# USB-C_BENCH_PSU.net
KiCad netlist of a schematic drawn in Altium Designer
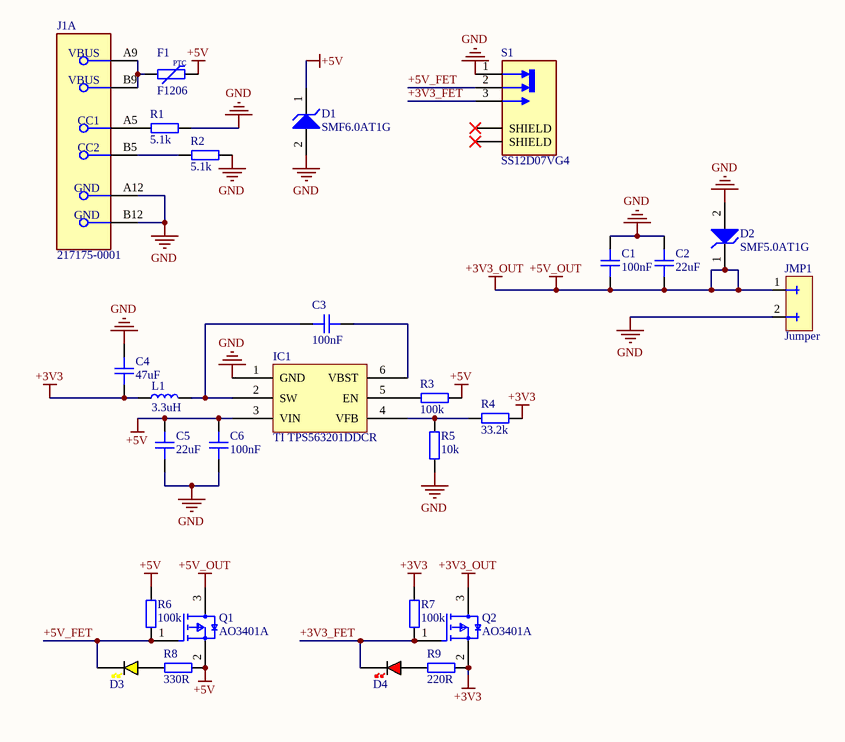
[diagram p0: USB-C_BENCH_PSU.SchDoc]

(export (version "E")
  (design (tool "Eeschema 10.0.6"))
  (components
    (comp (ref "C1")
      (value "100nF")
      (footprint "CAP_0402")
      (description "Capacitor SMD 0402")
      (libsource (lib "Schematic-Lib") (part "CAP_0402"))
    )
    (comp (ref "C2")
      (value "22uF")
      (footprint "CAP_0603")
      (description "Capacitor SMD 0603")
      (libsource (lib "Schematic-Lib") (part "CAP_0603"))
    )
    (comp (ref "C3")
      (value "100nF")
      (footprint "CAP_0402")
      (description "Capacitor SMD 0402")
      (libsource (lib "Schematic-Lib") (part "CAP_0402"))
    )
    (comp (ref "C4")
      (value "47uF")
      (footprint "CAP_0805")
      (description "Capacitor SMD 0805")
      (libsource (lib "Schematic-Lib") (part "CAP_0805"))
    )
    (comp (ref "C5")
      (value "22uF")
      (footprint "CAP_0603")
      (description "Capacitor SMD 0603")
      (libsource (lib "Schematic-Lib") (part "CAP_0603"))
    )
    (comp (ref "C6")
      (value "100nF")
      (footprint "CAP_0402")
      (description "Capacitor SMD 0402")
      (libsource (lib "Schematic-Lib") (part "CAP_0402"))
    )
    (comp (ref "D1")
      (value "SMF6.0AT1G")
      (footprint "ONSC-SOD-123FL-2-498_V")
      (description "200 W Transient Voltage Suppressor, 2-Pin SOD-123FL, Pb-Free, Tape and Reel")
      (fields (field (name "PARTNUMBER") "SMF5.0AT1G") (field (name "MANUFACTURER") "On Semiconductor"))
      (libsource (lib "Altium Content Vault") (part "ONSC-K1A2-2"))
    )
    (comp (ref "D2")
      (value "SMF5.0AT1G")
      (footprint "ONSC-SOD-123FL-2-498_V")
      (description "200 W Transient Voltage Suppressor, 2-Pin SOD-123FL, Pb-Free, Tape and Reel")
      (fields (field (name "MANUFACTURER") "On Semiconductor"))
      (libsource (lib "Altium Content Vault") (part "ONSC-K1A2-2"))
    )
    (comp (ref "D3")
      (value "WHITE")
      (footprint "LED_0603_YELLOW")
      (description "LED 0603 WHITE SMD")
      (libsource (lib "Schematic-Lib") (part "LED_0603_YELLOW"))
    )
    (comp (ref "D4")
      (value "RED")
      (footprint "LED_0603_RED")
      (description "LED 0603 RED SMD")
      (libsource (lib "Schematic-Lib") (part "LED_0603_RED"))
    )
    (comp (ref "F1")
      (value "F1206")
      (footprint "FUSE_1206")
      (description "Fuse PPTC SMD 1206")
      (libsource (lib "Schematic-Lib") (part "FUSE_PPTC_1206"))
    )
    (comp (ref "IC1")
      (value "TI TPS563201DDCR")
      (footprint "TI TPS563201DDCR")
      (libsource (lib "Custom_Components") (part "TI TPS563201DDCR"))
    )
    (comp (ref "J1")
      (value "217175-0001")
      (footprint "FP-217175-0001-MFG")
      (description "CONN RCP USB2.0 C 6+18P SMD RA")
      (libsource (lib "Altium Content Vault") (part "6a66c69350f09309f94811689c98437"))
    )
    (comp (ref "JMP1")
      (value "Jumper")
      (footprint "JMP2_TH")
      (description "Jumper 2 Pins Through-Hole DO NOT PLACE")
      (libsource (lib "Schematic-Lib") (part "JMP2_TH"))
    )
    (comp (ref "L1")
      (value "3.3uH")
      (footprint "IND_1008")
      (description "Inductor SMD 1008")
      (libsource (lib "Schematic-Lib") (part "IND_1008"))
    )
    (comp (ref "Q1")
      (value "AO3401A")
      (footprint "FP-SOT23-IPC_B")
      (description "MOSFET P-CH 30V SOT23")
      (libsource (lib "Altium Content Vault") (part "d876440acba04c58a9f817a20952145"))
    )
    (comp (ref "Q2")
      (value "AO3401A")
      (footprint "FP-SOT23-IPC_B")
      (description "MOSFET P-CH 30V SOT23")
      (libsource (lib "Altium Content Vault") (part "d876440acba04c58a9f817a20952145"))
    )
    (comp (ref "R1")
      (value "5.1k")
      (footprint "RES_0402")
      (description "Resistor SMD 0402")
      (libsource (lib "Schematic-Lib") (part "RES_0402"))
    )
    (comp (ref "R2")
      (value "5.1k")
      (footprint "RES_0402")
      (description "Resistor SMD 0402")
      (libsource (lib "Schematic-Lib") (part "RES_0402"))
    )
    (comp (ref "R3")
      (value "100k")
      (footprint "RES_0402")
      (description "Resistor SMD 0402")
      (libsource (lib "Schematic-Lib") (part "RES_0402"))
    )
    (comp (ref "R4")
      (value "33.2k")
      (footprint "RES_0402")
      (description "Resistor SMD 0402")
      (libsource (lib "Schematic-Lib") (part "RES_0402"))
    )
    (comp (ref "R5")
      (value "10k")
      (footprint "RES_0402")
      (description "Resistor SMD 0402")
      (libsource (lib "Schematic-Lib") (part "RES_0402"))
    )
    (comp (ref "R6")
      (value "100k")
      (footprint "RES_0402")
      (description "Resistor SMD 0402")
      (libsource (lib "Schematic-Lib") (part "RES_0402"))
    )
    (comp (ref "R7")
      (value "100k")
      (footprint "RES_0402")
      (description "Resistor SMD 0402")
      (libsource (lib "Schematic-Lib") (part "RES_0402"))
    )
    (comp (ref "R8")
      (value "330R")
      (footprint "RES_0402")
      (description "Resistor SMD 0402")
      (libsource (lib "Schematic-Lib") (part "RES_0402"))
    )
    (comp (ref "R9")
      (value "220R")
      (footprint "RES_0402")
      (description "Resistor SMD 0402")
      (libsource (lib "Schematic-Lib") (part "RES_0402"))
    )
    (comp (ref "S1")
      (value "SS12D07VG4")
      (footprint "SW_SS12D07VG4")
      (description "Switch Slide ON ON SPDT Top Slide 0.3A 30VDC PC Pins Bracket Mount/Through Hole Automotive Bulk")
      (fields (field (name "MF") "Shouhan"))
      (libsource (lib "SS12D07VG4") (part "SS12D07VG4"))
    )
  )
  (nets
    (net (code "1") (name "+3V3") (class "Default")
      (node (ref "C4") (pin "1") (pinfunction "1_1") (pintype "passive"))
      (node (ref "L1") (pin "1") (pinfunction "1_1") (pintype "passive"))
      (node (ref "Q2") (pin "2") (pinfunction "S_2") (pintype "passive"))
      (node (ref "R4") (pin "2") (pinfunction "2_2") (pintype "passive"))
      (node (ref "R7") (pin "2") (pinfunction "2_2") (pintype "passive"))
      (node (ref "R9") (pin "2") (pinfunction "2_2") (pintype "passive"))
    )
    (net (code "2") (name "+3V3_OUT") (class "Default")
      (node (ref "C1") (pin "1") (pinfunction "1_1") (pintype "passive"))
      (node (ref "C2") (pin "1") (pinfunction "1_1") (pintype "passive"))
      (node (ref "D2") (pin "1") (pinfunction "K_1") (pintype "passive"))
      (node (ref "JMP1") (pin "1") (pinfunction "1_1") (pintype "passive"))
      (node (ref "Q1") (pin "3") (pinfunction "D_3") (pintype "passive"))
      (node (ref "Q2") (pin "3") (pinfunction "D_3") (pintype "passive"))
    )
    (net (code "3") (name "+5V") (class "Default")
      (node (ref "C5") (pin "1") (pinfunction "1_1") (pintype "passive"))
      (node (ref "C6") (pin "1") (pinfunction "1_1") (pintype "passive"))
      (node (ref "D1") (pin "1") (pinfunction "K_1") (pintype "passive"))
      (node (ref "F1") (pin "2") (pinfunction "2_2") (pintype "passive"))
      (node (ref "IC1") (pin "3") (pinfunction "VIN_3") (pintype "passive"))
      (node (ref "Q1") (pin "2") (pinfunction "S_2") (pintype "passive"))
      (node (ref "R3") (pin "2") (pinfunction "2_2") (pintype "passive"))
      (node (ref "R6") (pin "2") (pinfunction "2_2") (pintype "passive"))
      (node (ref "R8") (pin "2") (pinfunction "2_2") (pintype "passive"))
    )
    (net (code "4") (name "/+3V3_FET") (class "Default")
      (node (ref "D4") (pin "K") (pinfunction "K_K") (pintype "passive"))
      (node (ref "Q2") (pin "1") (pinfunction "G_1") (pintype "passive"))
      (node (ref "R7") (pin "1") (pinfunction "1_1") (pintype "passive"))
      (node (ref "S1") (pin "3") (pinfunction "3_3") (pintype "passive"))
    )
    (net (code "5") (name "/+5V_FET") (class "Default")
      (node (ref "D3") (pin "K") (pinfunction "K_K") (pintype "passive"))
      (node (ref "Q1") (pin "1") (pinfunction "G_1") (pintype "passive"))
      (node (ref "R6") (pin "1") (pinfunction "1_1") (pintype "passive"))
      (node (ref "S1") (pin "2") (pinfunction "2_2") (pintype "passive"))
    )
    (net (code "6") (name "GND") (class "Default")
      (node (ref "C1") (pin "2") (pinfunction "2_2") (pintype "passive"))
      (node (ref "C2") (pin "2") (pinfunction "2_2") (pintype "passive"))
      (node (ref "C4") (pin "2") (pinfunction "2_2") (pintype "passive"))
      (node (ref "C5") (pin "2") (pinfunction "2_2") (pintype "passive"))
      (node (ref "C6") (pin "2") (pinfunction "2_2") (pintype "passive"))
      (node (ref "D1") (pin "2") (pinfunction "A_2") (pintype "passive"))
      (node (ref "D2") (pin "2") (pinfunction "A_2") (pintype "passive"))
      (node (ref "IC1") (pin "1") (pinfunction "GND_1") (pintype "passive"))
      (node (ref "J1") (pin "A12") (pinfunction "GND_A12") (pintype "power_in"))
      (node (ref "J1") (pin "B12") (pinfunction "GND_B12") (pintype "power_in"))
      (node (ref "JMP1") (pin "2") (pinfunction "2_2") (pintype "passive"))
      (node (ref "R1") (pin "2") (pinfunction "2_2") (pintype "passive"))
      (node (ref "R2") (pin "2") (pinfunction "2_2") (pintype "passive"))
      (node (ref "R5") (pin "1") (pinfunction "1_1") (pintype "passive"))
      (node (ref "S1") (pin "1") (pinfunction "1_1") (pintype "passive"))
    )
    (net (code "7") (name "Net-(D3-PadA)") (class "Default")
      (node (ref "D3") (pin "A") (pinfunction "A_A") (pintype "passive"))
      (node (ref "R8") (pin "1") (pinfunction "1_1") (pintype "passive"))
    )
    (net (code "8") (name "Net-(D4-PadA)") (class "Default")
      (node (ref "D4") (pin "A") (pinfunction "A_A") (pintype "passive"))
      (node (ref "R9") (pin "1") (pinfunction "1_1") (pintype "passive"))
    )
    (net (code "9") (name "Net-(F1-Pad1)") (class "Default")
      (node (ref "F1") (pin "1") (pinfunction "1_1") (pintype "passive"))
      (node (ref "J1") (pin "A9") (pinfunction "VBUS_A9") (pintype "power_in"))
      (node (ref "J1") (pin "B9") (pinfunction "VBUS_B9") (pintype "power_in"))
    )
    (net (code "10") (name "Net-(IC1-EN)") (class "Default")
      (node (ref "IC1") (pin "5") (pinfunction "EN_5") (pintype "passive"))
      (node (ref "R3") (pin "1") (pinfunction "1_1") (pintype "passive"))
    )
    (net (code "11") (name "Net-(IC1-SW)") (class "Default")
      (node (ref "C3") (pin "2") (pinfunction "2_2") (pintype "passive"))
      (node (ref "IC1") (pin "2") (pinfunction "SW_2") (pintype "passive"))
      (node (ref "L1") (pin "2") (pinfunction "2_2") (pintype "passive"))
    )
    (net (code "12") (name "Net-(IC1-VBST)") (class "Default")
      (node (ref "C3") (pin "1") (pinfunction "1_1") (pintype "passive"))
      (node (ref "IC1") (pin "6") (pinfunction "VBST_6") (pintype "passive"))
    )
    (net (code "13") (name "Net-(IC1-VFB)") (class "Default")
      (node (ref "IC1") (pin "4") (pinfunction "VFB_4") (pintype "passive"))
      (node (ref "R4") (pin "1") (pinfunction "1_1") (pintype "passive"))
      (node (ref "R5") (pin "2") (pinfunction "2_2") (pintype "passive"))
    )
    (net (code "14") (name "Net-(J1A-CC1)") (class "Default")
      (node (ref "J1") (pin "A5") (pinfunction "CC1_A5") (pintype "passive"))
      (node (ref "R1") (pin "1") (pinfunction "1_1") (pintype "passive"))
    )
    (net (code "15") (name "Net-(J1A-CC2)") (class "Default")
      (node (ref "J1") (pin "B5") (pinfunction "CC2_B5") (pintype "passive"))
      (node (ref "R2") (pin "1") (pinfunction "1_1") (pintype "passive"))
    )
    (net (code "16") (name "unconnected-(S1-SHIELD-PadS1)") (class "Default")
      (node (ref "S1") (pin "S1") (pinfunction "SHIELD_S1") (pintype "passive+no_connect"))
    )
    (net (code "17") (name "unconnected-(S1-SHIELD-PadS2)") (class "Default")
      (node (ref "S1") (pin "S2") (pinfunction "SHIELD_S2") (pintype "passive+no_connect"))
    )
  )
)
